# TC377TP_2.net
KiCad netlist of a schematic drawn in Altium Designer
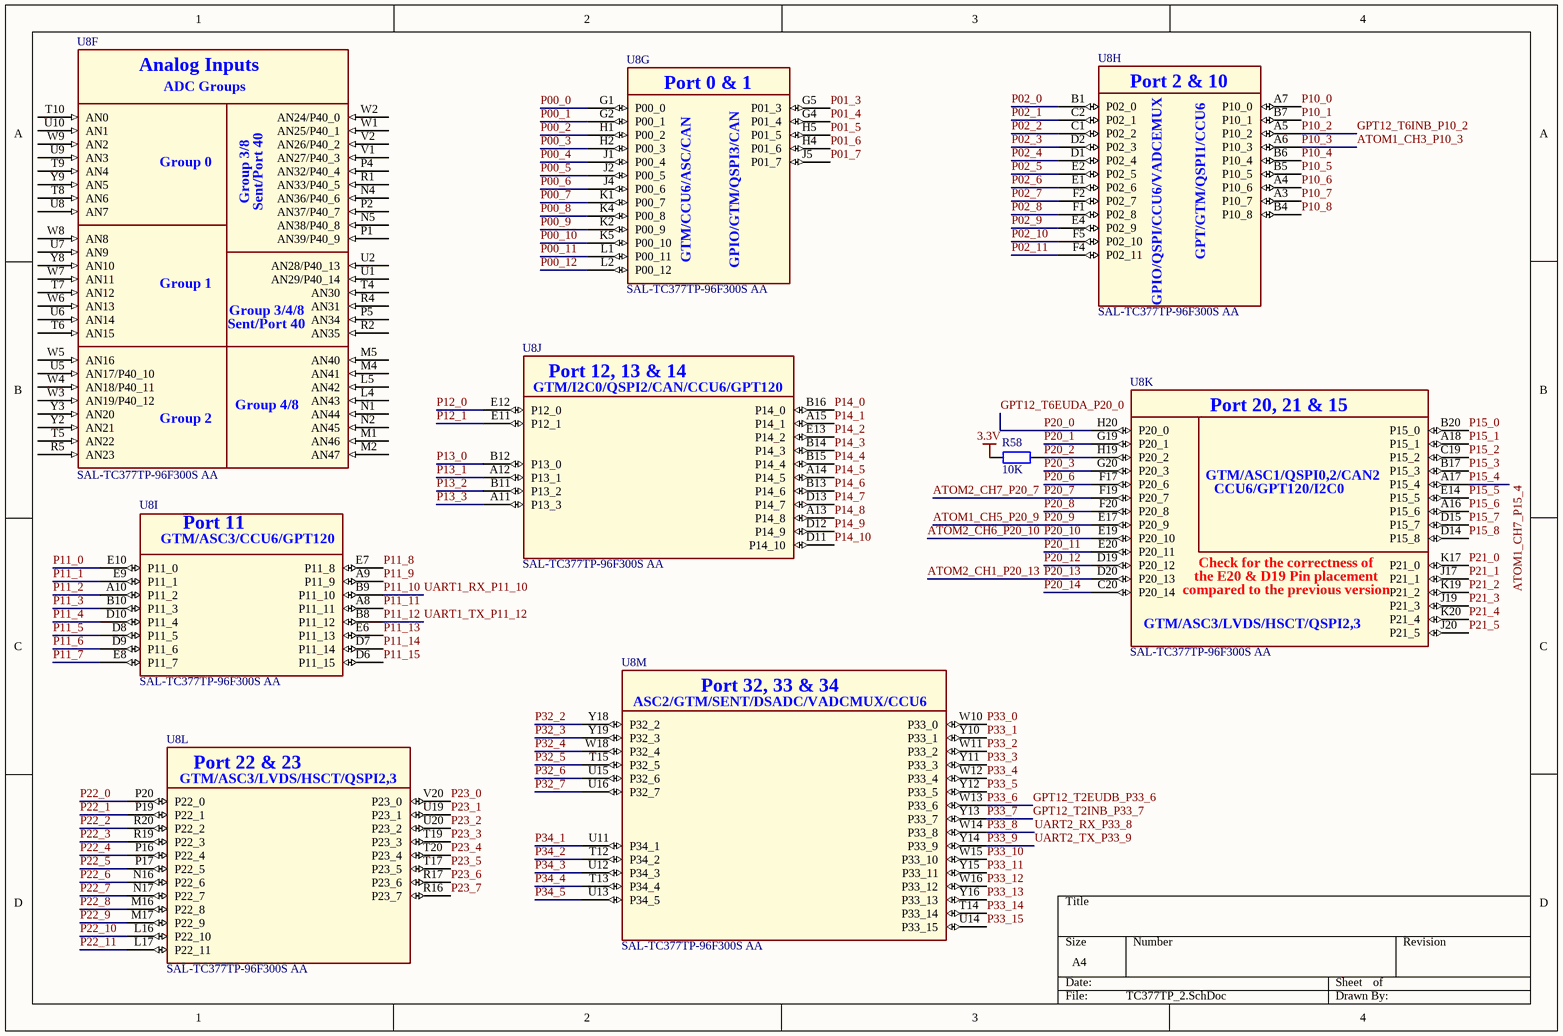
[diagram p0: TC377TP_2.SchDoc]

(export (version "E")
  (design (tool "Eeschema 10.0.6"))
  (components
    (comp (ref "R58")
      (value "10K")
      (footprint "R 0603_L")
      (description "贴片电阻")
      (fields (field (name "版权归属") "源创客"))
      (libsource (lib "3.1   - 电阻-电容-电感") (part "R"))
    )
    (comp (ref "U8")
      (value "SAL-TC377TP-96F300S AA")
      (footprint "BGA292C80P20X20")
      (description "32-Bit Single-Chip Microcontroller")
      (fields (field (name "MANUFACTURER") "Infineon Technologies"))
      (libsource (lib "SAL-TC377TP-96F300S AA") (part "SAL-TC377TP-96F300S AA"))
    )
  )
  (nets
    (net (code "1") (name "/ATOM1_CH3_P10_3") (class "Default")
      (node (ref "U8") (pin "A6") (pinfunction "P10_3_A6") (pintype "bidirectional"))
    )
    (net (code "2") (name "/ATOM1_CH5_P20_9") (class "Default")
      (node (ref "U8") (pin "E17") (pinfunction "P20_9_E17") (pintype "bidirectional"))
    )
    (net (code "3") (name "/ATOM1_CH7_P15_4") (class "Default")
      (node (ref "U8") (pin "A17") (pinfunction "P15_4_A17") (pintype "bidirectional"))
    )
    (net (code "4") (name "/ATOM2_CH1_P20_13") (class "Default")
      (node (ref "U8") (pin "D20") (pinfunction "P20_13_D20") (pintype "bidirectional"))
    )
    (net (code "5") (name "/ATOM2_CH6_P20_10") (class "Default")
      (node (ref "U8") (pin "E19") (pinfunction "P20_10_E19") (pintype "bidirectional"))
    )
    (net (code "6") (name "/ATOM2_CH7_P20_7") (class "Default")
      (node (ref "U8") (pin "F19") (pinfunction "P20_7_F19") (pintype "bidirectional"))
    )
    (net (code "7") (name "/GPT12_T2EUDB_P33_6") (class "Default")
      (node (ref "U8") (pin "W13") (pinfunction "P33_6_W13") (pintype "bidirectional"))
    )
    (net (code "8") (name "/GPT12_T2INB_P33_7") (class "Default")
      (node (ref "U8") (pin "Y13") (pinfunction "P33_7_Y13") (pintype "bidirectional"))
    )
    (net (code "9") (name "/GPT12_T6EUDA_P20_0") (class "Default")
      (node (ref "U8") (pin "H20") (pinfunction "P20_0_H20") (pintype "bidirectional"))
    )
    (net (code "10") (name "/GPT12_T6INB_P10_2") (class "Default")
      (node (ref "U8") (pin "A5") (pinfunction "P10_2_A5") (pintype "bidirectional"))
    )
    (net (code "11") (name "/P00_0") (class "Default")
      (node (ref "U8") (pin "G1") (pinfunction "P00_0_G1") (pintype "bidirectional"))
    )
    (net (code "12") (name "/P00_1") (class "Default")
      (node (ref "U8") (pin "G2") (pinfunction "P00_1_G2") (pintype "bidirectional"))
    )
    (net (code "13") (name "/P00_2") (class "Default")
      (node (ref "U8") (pin "H1") (pinfunction "P00_2_H1") (pintype "bidirectional"))
    )
    (net (code "14") (name "/P00_3") (class "Default")
      (node (ref "U8") (pin "H2") (pinfunction "P00_3_H2") (pintype "bidirectional"))
    )
    (net (code "15") (name "/P00_4") (class "Default")
      (node (ref "U8") (pin "J1") (pinfunction "P00_4_J1") (pintype "bidirectional"))
    )
    (net (code "16") (name "/P00_5") (class "Default")
      (node (ref "U8") (pin "J2") (pinfunction "P00_5_J2") (pintype "bidirectional"))
    )
    (net (code "17") (name "/P00_6") (class "Default")
      (node (ref "U8") (pin "J4") (pinfunction "P00_6_J4") (pintype "bidirectional"))
    )
    (net (code "18") (name "/P00_7") (class "Default")
      (node (ref "U8") (pin "K1") (pinfunction "P00_7_K1") (pintype "bidirectional"))
    )
    (net (code "19") (name "/P00_8") (class "Default")
      (node (ref "U8") (pin "K4") (pinfunction "P00_8_K4") (pintype "bidirectional"))
    )
    (net (code "20") (name "/P00_9") (class "Default")
      (node (ref "U8") (pin "K2") (pinfunction "P00_9_K2") (pintype "bidirectional"))
    )
    (net (code "21") (name "/P00_10") (class "Default")
      (node (ref "U8") (pin "K5") (pinfunction "P00_10_K5") (pintype "bidirectional"))
    )
    (net (code "22") (name "/P00_11") (class "Default")
      (node (ref "U8") (pin "L1") (pinfunction "P00_11_L1") (pintype "bidirectional"))
    )
    (net (code "23") (name "/P00_12") (class "Default")
      (node (ref "U8") (pin "L2") (pinfunction "P00_12_L2") (pintype "bidirectional"))
    )
    (net (code "24") (name "/P01_3") (class "Default")
      (node (ref "U8") (pin "G5") (pinfunction "P01_3_G5") (pintype "bidirectional"))
    )
    (net (code "25") (name "/P01_4") (class "Default")
      (node (ref "U8") (pin "G4") (pinfunction "P01_4_G4") (pintype "bidirectional"))
    )
    (net (code "26") (name "/P01_5") (class "Default")
      (node (ref "U8") (pin "H5") (pinfunction "P01_5_H5") (pintype "bidirectional"))
    )
    (net (code "27") (name "/P01_6") (class "Default")
      (node (ref "U8") (pin "H4") (pinfunction "P01_6_H4") (pintype "bidirectional"))
    )
    (net (code "28") (name "/P01_7") (class "Default")
      (node (ref "U8") (pin "J5") (pinfunction "P01_7_J5") (pintype "bidirectional"))
    )
    (net (code "29") (name "/P02_0") (class "Default")
      (node (ref "U8") (pin "B1") (pinfunction "P02_0_B1") (pintype "bidirectional"))
    )
    (net (code "30") (name "/P02_1") (class "Default")
      (node (ref "U8") (pin "C2") (pinfunction "P02_1_C2") (pintype "bidirectional"))
    )
    (net (code "31") (name "/P02_2") (class "Default")
      (node (ref "U8") (pin "C1") (pinfunction "P02_2_C1") (pintype "bidirectional"))
    )
    (net (code "32") (name "/P02_3") (class "Default")
      (node (ref "U8") (pin "D2") (pinfunction "P02_3_D2") (pintype "bidirectional"))
    )
    (net (code "33") (name "/P02_4") (class "Default")
      (node (ref "U8") (pin "D1") (pinfunction "P02_4_D1") (pintype "bidirectional"))
    )
    (net (code "34") (name "/P02_5") (class "Default")
      (node (ref "U8") (pin "E2") (pinfunction "P02_5_E2") (pintype "bidirectional"))
    )
    (net (code "35") (name "/P02_6") (class "Default")
      (node (ref "U8") (pin "E1") (pinfunction "P02_6_E1") (pintype "bidirectional"))
    )
    (net (code "36") (name "/P02_7") (class "Default")
      (node (ref "U8") (pin "F2") (pinfunction "P02_7_F2") (pintype "bidirectional"))
    )
    (net (code "37") (name "/P02_8") (class "Default")
      (node (ref "U8") (pin "F1") (pinfunction "P02_8_F1") (pintype "bidirectional"))
    )
    (net (code "38") (name "/P02_9") (class "Default")
      (node (ref "U8") (pin "E4") (pinfunction "P02_9_E4") (pintype "bidirectional"))
    )
    (net (code "39") (name "/P02_10") (class "Default")
      (node (ref "U8") (pin "F5") (pinfunction "P02_10_F5") (pintype "bidirectional"))
    )
    (net (code "40") (name "/P02_11") (class "Default")
      (node (ref "U8") (pin "F4") (pinfunction "P02_11_F4") (pintype "bidirectional"))
    )
    (net (code "41") (name "/P10_0") (class "Default")
      (node (ref "U8") (pin "A7") (pinfunction "P10_0_A7") (pintype "bidirectional"))
    )
    (net (code "42") (name "/P10_1") (class "Default")
      (node (ref "U8") (pin "B7") (pinfunction "P10_1_B7") (pintype "bidirectional"))
    )
    (net (code "43") (name "/P10_4") (class "Default")
      (node (ref "U8") (pin "B6") (pinfunction "P10_4_B6") (pintype "bidirectional"))
    )
    (net (code "44") (name "/P10_5") (class "Default")
      (node (ref "U8") (pin "B5") (pinfunction "P10_5_B5") (pintype "bidirectional"))
    )
    (net (code "45") (name "/P10_6") (class "Default")
      (node (ref "U8") (pin "A4") (pinfunction "P10_6_A4") (pintype "bidirectional"))
    )
    (net (code "46") (name "/P10_7") (class "Default")
      (node (ref "U8") (pin "A3") (pinfunction "P10_7_A3") (pintype "bidirectional"))
    )
    (net (code "47") (name "/P10_8") (class "Default")
      (node (ref "U8") (pin "B4") (pinfunction "P10_8_B4") (pintype "bidirectional"))
    )
    (net (code "48") (name "/P11_0") (class "Default")
      (node (ref "U8") (pin "E10") (pinfunction "P11_0_E10") (pintype "bidirectional"))
    )
    (net (code "49") (name "/P11_1") (class "Default")
      (node (ref "U8") (pin "E9") (pinfunction "P11_1_E9") (pintype "bidirectional"))
    )
    (net (code "50") (name "/P11_2") (class "Default")
      (node (ref "U8") (pin "A10") (pinfunction "P11_2_A10") (pintype "bidirectional"))
    )
    (net (code "51") (name "/P11_3") (class "Default")
      (node (ref "U8") (pin "B10") (pinfunction "P11_3_B10") (pintype "bidirectional"))
    )
    (net (code "52") (name "/P11_4") (class "Default")
      (node (ref "U8") (pin "D10") (pinfunction "P11_4_D10") (pintype "bidirectional"))
    )
    (net (code "53") (name "/P11_5") (class "Default")
      (node (ref "U8") (pin "D8") (pinfunction "P11_5_D8") (pintype "bidirectional"))
    )
    (net (code "54") (name "/P11_6") (class "Default")
      (node (ref "U8") (pin "D9") (pinfunction "P11_6_D9") (pintype "bidirectional"))
    )
    (net (code "55") (name "/P11_7") (class "Default")
      (node (ref "U8") (pin "E8") (pinfunction "P11_7_E8") (pintype "bidirectional"))
    )
    (net (code "56") (name "/P11_8") (class "Default")
      (node (ref "U8") (pin "E7") (pinfunction "P11_8_E7") (pintype "bidirectional"))
    )
    (net (code "57") (name "/P11_9") (class "Default")
      (node (ref "U8") (pin "A9") (pinfunction "P11_9_A9") (pintype "bidirectional"))
    )
    (net (code "58") (name "/P11_10") (class "Default")
      (node (ref "U8") (pin "B9") (pinfunction "P11_10_B9") (pintype "bidirectional"))
    )
    (net (code "59") (name "/P11_11") (class "Default")
      (node (ref "U8") (pin "A8") (pinfunction "P11_11_A8") (pintype "bidirectional"))
    )
    (net (code "60") (name "/P11_12") (class "Default")
      (node (ref "U8") (pin "B8") (pinfunction "P11_12_B8") (pintype "bidirectional"))
    )
    (net (code "61") (name "/P11_13") (class "Default")
      (node (ref "U8") (pin "E6") (pinfunction "P11_13_E6") (pintype "bidirectional"))
    )
    (net (code "62") (name "/P11_14") (class "Default")
      (node (ref "U8") (pin "D7") (pinfunction "P11_14_D7") (pintype "bidirectional"))
    )
    (net (code "63") (name "/P11_15") (class "Default")
      (node (ref "U8") (pin "D6") (pinfunction "P11_15_D6") (pintype "bidirectional"))
    )
    (net (code "64") (name "/P12_0") (class "Default")
      (node (ref "U8") (pin "E12") (pinfunction "P12_0_E12") (pintype "bidirectional"))
    )
    (net (code "65") (name "/P12_1") (class "Default")
      (node (ref "U8") (pin "E11") (pinfunction "P12_1_E11") (pintype "bidirectional"))
    )
    (net (code "66") (name "/P13_0") (class "Default")
      (node (ref "U8") (pin "B12") (pinfunction "P13_0_B12") (pintype "bidirectional"))
    )
    (net (code "67") (name "/P13_1") (class "Default")
      (node (ref "U8") (pin "A12") (pinfunction "P13_1_A12") (pintype "bidirectional"))
    )
    (net (code "68") (name "/P13_2") (class "Default")
      (node (ref "U8") (pin "B11") (pinfunction "P13_2_B11") (pintype "bidirectional"))
    )
    (net (code "69") (name "/P13_3") (class "Default")
      (node (ref "U8") (pin "A11") (pinfunction "P13_3_A11") (pintype "bidirectional"))
    )
    (net (code "70") (name "/P14_0") (class "Default")
      (node (ref "U8") (pin "B16") (pinfunction "P14_0_B16") (pintype "bidirectional"))
    )
    (net (code "71") (name "/P14_1") (class "Default")
      (node (ref "U8") (pin "A15") (pinfunction "P14_1_A15") (pintype "bidirectional"))
    )
    (net (code "72") (name "/P14_2") (class "Default")
      (node (ref "U8") (pin "E13") (pinfunction "P14_2_E13") (pintype "bidirectional"))
    )
    (net (code "73") (name "/P14_3") (class "Default")
      (node (ref "U8") (pin "B14") (pinfunction "P14_3_B14") (pintype "bidirectional"))
    )
    (net (code "74") (name "/P14_4") (class "Default")
      (node (ref "U8") (pin "B15") (pinfunction "P14_4_B15") (pintype "bidirectional"))
    )
    (net (code "75") (name "/P14_5") (class "Default")
      (node (ref "U8") (pin "A14") (pinfunction "P14_5_A14") (pintype "bidirectional"))
    )
    (net (code "76") (name "/P14_6") (class "Default")
      (node (ref "U8") (pin "B13") (pinfunction "P14_6_B13") (pintype "bidirectional"))
    )
    (net (code "77") (name "/P14_7") (class "Default")
      (node (ref "U8") (pin "D13") (pinfunction "P14_7_D13") (pintype "bidirectional"))
    )
    (net (code "78") (name "/P14_8") (class "Default")
      (node (ref "U8") (pin "A13") (pinfunction "P14_8_A13") (pintype "bidirectional"))
    )
    (net (code "79") (name "/P14_9") (class "Default")
      (node (ref "U8") (pin "D12") (pinfunction "P14_9_D12") (pintype "bidirectional"))
    )
    (net (code "80") (name "/P14_10") (class "Default")
      (node (ref "U8") (pin "D11") (pinfunction "P14_10_D11") (pintype "bidirectional"))
    )
    (net (code "81") (name "/P15_0") (class "Default")
      (node (ref "U8") (pin "B20") (pinfunction "P15_0_B20") (pintype "bidirectional"))
    )
    (net (code "82") (name "/P15_1") (class "Default")
      (node (ref "U8") (pin "A18") (pinfunction "P15_1_A18") (pintype "bidirectional"))
    )
    (net (code "83") (name "/P15_2") (class "Default")
      (node (ref "U8") (pin "C19") (pinfunction "P15_2_C19") (pintype "bidirectional"))
    )
    (net (code "84") (name "/P15_3") (class "Default")
      (node (ref "U8") (pin "B17") (pinfunction "P15_3_B17") (pintype "bidirectional"))
    )
    (net (code "85") (name "/P15_5") (class "Default")
      (node (ref "U8") (pin "E14") (pinfunction "P15_5_E14") (pintype "bidirectional"))
    )
    (net (code "86") (name "/P15_6") (class "Default")
      (node (ref "U8") (pin "A16") (pinfunction "P15_6_A16") (pintype "bidirectional"))
    )
    (net (code "87") (name "/P15_7") (class "Default")
      (node (ref "U8") (pin "D15") (pinfunction "P15_7_D15") (pintype "bidirectional"))
    )
    (net (code "88") (name "/P15_8") (class "Default")
      (node (ref "U8") (pin "D14") (pinfunction "P15_8_D14") (pintype "bidirectional"))
    )
    (net (code "89") (name "/P20_1") (class "Default")
      (node (ref "U8") (pin "G19") (pinfunction "P20_1_G19") (pintype "bidirectional"))
    )
    (net (code "90") (name "/P20_2") (class "Default")
      (node (ref "R58") (pin "1") (pinfunction "1_1") (pintype "passive"))
      (node (ref "U8") (pin "H19") (pinfunction "P20_2_H19") (pintype "bidirectional"))
    )
    (net (code "91") (name "/P20_3") (class "Default")
      (node (ref "U8") (pin "G20") (pinfunction "P20_3_G20") (pintype "bidirectional"))
    )
    (net (code "92") (name "/P20_6") (class "Default")
      (node (ref "U8") (pin "F17") (pinfunction "P20_6_F17") (pintype "bidirectional"))
    )
    (net (code "93") (name "/P20_8") (class "Default")
      (node (ref "U8") (pin "F20") (pinfunction "P20_8_F20") (pintype "bidirectional"))
    )
    (net (code "94") (name "/P20_11") (class "Default")
      (node (ref "U8") (pin "E20") (pinfunction "P20_11_E20") (pintype "bidirectional"))
    )
    (net (code "95") (name "/P20_12") (class "Default")
      (node (ref "U8") (pin "D19") (pinfunction "P20_12_D19") (pintype "bidirectional"))
    )
    (net (code "96") (name "/P20_14") (class "Default")
      (node (ref "U8") (pin "C20") (pinfunction "P20_14_C20") (pintype "bidirectional"))
    )
    (net (code "97") (name "/P21_0") (class "Default")
      (node (ref "U8") (pin "K17") (pinfunction "P21_0_K17") (pintype "bidirectional"))
    )
    (net (code "98") (name "/P21_1") (class "Default")
      (node (ref "U8") (pin "J17") (pinfunction "P21_1_J17") (pintype "bidirectional"))
    )
    (net (code "99") (name "/P21_2") (class "Default")
      (node (ref "U8") (pin "K19") (pinfunction "P21_2_K19") (pintype "bidirectional"))
    )
    (net (code "100") (name "/P21_3") (class "Default")
      (node (ref "U8") (pin "J19") (pinfunction "P21_3_J19") (pintype "bidirectional"))
    )
    (net (code "101") (name "/P21_4") (class "Default")
      (node (ref "U8") (pin "K20") (pinfunction "P21_4_K20") (pintype "bidirectional"))
    )
    (net (code "102") (name "/P21_5") (class "Default")
      (node (ref "U8") (pin "J20") (pinfunction "P21_5_J20") (pintype "bidirectional"))
    )
    (net (code "103") (name "/P22_0") (class "Default")
      (node (ref "U8") (pin "P20") (pinfunction "P22_0_P20") (pintype "bidirectional"))
    )
    (net (code "104") (name "/P22_1") (class "Default")
      (node (ref "U8") (pin "P19") (pinfunction "P22_1_P19") (pintype "bidirectional"))
    )
    (net (code "105") (name "/P22_2") (class "Default")
      (node (ref "U8") (pin "R20") (pinfunction "P22_2_R20") (pintype "bidirectional"))
    )
    (net (code "106") (name "/P22_3") (class "Default")
      (node (ref "U8") (pin "R19") (pinfunction "P22_3_R19") (pintype "bidirectional"))
    )
    (net (code "107") (name "/P22_4") (class "Default")
      (node (ref "U8") (pin "P16") (pinfunction "P22_4_P16") (pintype "bidirectional"))
    )
    (net (code "108") (name "/P22_5") (class "Default")
      (node (ref "U8") (pin "P17") (pinfunction "P22_5_P17") (pintype "bidirectional"))
    )
    (net (code "109") (name "/P22_6") (class "Default")
      (node (ref "U8") (pin "N16") (pinfunction "P22_6_N16") (pintype "bidirectional"))
    )
    (net (code "110") (name "/P22_7") (class "Default")
      (node (ref "U8") (pin "N17") (pinfunction "P22_7_N17") (pintype "bidirectional"))
    )
    (net (code "111") (name "/P22_8") (class "Default")
      (node (ref "U8") (pin "M16") (pinfunction "P22_8_M16") (pintype "bidirectional"))
    )
    (net (code "112") (name "/P22_9") (class "Default")
      (node (ref "U8") (pin "M17") (pinfunction "P22_9_M17") (pintype "bidirectional"))
    )
    (net (code "113") (name "/P22_10") (class "Default")
      (node (ref "U8") (pin "L16") (pinfunction "P22_10_L16") (pintype "bidirectional"))
    )
    (net (code "114") (name "/P22_11") (class "Default")
      (node (ref "U8") (pin "L17") (pinfunction "P22_11_L17") (pintype "bidirectional"))
    )
    (net (code "115") (name "/P23_0") (class "Default")
      (node (ref "U8") (pin "V20") (pinfunction "P23_0_V20") (pintype "bidirectional"))
    )
    (net (code "116") (name "/P23_1") (class "Default")
      (node (ref "U8") (pin "U19") (pinfunction "P23_1_U19") (pintype "bidirectional"))
    )
    (net (code "117") (name "/P23_2") (class "Default")
      (node (ref "U8") (pin "U20") (pinfunction "P23_2_U20") (pintype "bidirectional"))
    )
    (net (code "118") (name "/P23_3") (class "Default")
      (node (ref "U8") (pin "T19") (pinfunction "P23_3_T19") (pintype "bidirectional"))
    )
    (net (code "119") (name "/P23_4") (class "Default")
      (node (ref "U8") (pin "T20") (pinfunction "P23_4_T20") (pintype "bidirectional"))
    )
    (net (code "120") (name "/P23_5") (class "Default")
      (node (ref "U8") (pin "T17") (pinfunction "P23_5_T17") (pintype "bidirectional"))
    )
    (net (code "121") (name "/P23_6") (class "Default")
      (node (ref "U8") (pin "R17") (pinfunction "P23_6_R17") (pintype "bidirectional"))
    )
    (net (code "122") (name "/P23_7") (class "Default")
      (node (ref "U8") (pin "R16") (pinfunction "P23_7_R16") (pintype "bidirectional"))
    )
    (net (code "123") (name "/P32_2") (class "Default")
      (node (ref "U8") (pin "Y18") (pinfunction "P32_2_Y18") (pintype "bidirectional"))
    )
    (net (code "124") (name "/P32_3") (class "Default")
      (node (ref "U8") (pin "Y19") (pinfunction "P32_3_Y19") (pintype "bidirectional"))
    )
    (net (code "125") (name "/P32_4") (class "Default")
      (node (ref "U8") (pin "W18") (pinfunction "P32_4_W18") (pintype "bidirectional"))
    )
    (net (code "126") (name "/P32_5") (class "Default")
      (node (ref "U8") (pin "T15") (pinfunction "P32_5_T15") (pintype "bidirectional"))
    )
    (net (code "127") (name "/P32_6") (class "Default")
      (node (ref "U8") (pin "U15") (pinfunction "P32_6_U15") (pintype "bidirectional"))
    )
    (net (code "128") (name "/P32_7") (class "Default")
      (node (ref "U8") (pin "U16") (pinfunction "P32_7_U16") (pintype "bidirectional"))
    )
    (net (code "129") (name "/P33_0") (class "Default")
      (node (ref "U8") (pin "W10") (pinfunction "P33_0_W10") (pintype "bidirectional"))
    )
    (net (code "130") (name "/P33_1") (class "Default")
      (node (ref "U8") (pin "Y10") (pinfunction "P33_1_Y10") (pintype "bidirectional"))
    )
    (net (code "131") (name "/P33_2") (class "Default")
      (node (ref "U8") (pin "W11") (pinfunction "P33_2_W11") (pintype "bidirectional"))
    )
    (net (code "132") (name "/P33_3") (class "Default")
      (node (ref "U8") (pin "Y11") (pinfunction "P33_3_Y11") (pintype "bidirectional"))
    )
    (net (code "133") (name "/P33_4") (class "Default")
      (node (ref "U8") (pin "W12") (pinfunction "P33_4_W12") (pintype "bidirectional"))
    )
    (net (code "134") (name "/P33_5") (class "Default")
      (node (ref "U8") (pin "Y12") (pinfunction "P33_5_Y12") (pintype "bidirectional"))
    )
    (net (code "135") (name "/P33_8") (class "Default")
      (node (ref "U8") (pin "W14") (pinfunction "P33_8_W14") (pintype "bidirectional"))
    )
    (net (code "136") (name "/P33_9") (class "Default")
      (node (ref "U8") (pin "Y14") (pinfunction "P33_9_Y14") (pintype "bidirectional"))
    )
    (net (code "137") (name "/P33_10") (class "Default")
      (node (ref "U8") (pin "W15") (pinfunction "P33_10_W15") (pintype "bidirectional"))
    )
    (net (code "138") (name "/P33_11") (class "Default")
      (node (ref "U8") (pin "Y15") (pinfunction "P33_11_Y15") (pintype "bidirectional"))
    )
    (net (code "139") (name "/P33_12") (class "Default")
      (node (ref "U8") (pin "W16") (pinfunction "P33_12_W16") (pintype "bidirectional"))
    )
    (net (code "140") (name "/P33_13") (class "Default")
      (node (ref "U8") (pin "Y16") (pinfunction "P33_13_Y16") (pintype "bidirectional"))
    )
    (net (code "141") (name "/P33_14") (class "Default")
      (node (ref "U8") (pin "T14") (pinfunction "P33_14_T14") (pintype "bidirectional"))
    )
    (net (code "142") (name "/P33_15") (class "Default")
      (node (ref "U8") (pin "U14") (pinfunction "P33_15_U14") (pintype "bidirectional"))
    )
    (net (code "143") (name "/P34_1") (class "Default")
      (node (ref "U8") (pin "U11") (pinfunction "P34_1_U11") (pintype "bidirectional"))
    )
    (net (code "144") (name "/P34_2") (class "Default")
      (node (ref "U8") (pin "T12") (pinfunction "P34_2_T12") (pintype "bidirectional"))
    )
    (net (code "145") (name "/P34_3") (class "Default")
      (node (ref "U8") (pin "U12") (pinfunction "P34_3_U12") (pintype "bidirectional"))
    )
    (net (code "146") (name "/P34_4") (class "Default")
      (node (ref "U8") (pin "T13") (pinfunction "P34_4_T13") (pintype "bidirectional"))
    )
    (net (code "147") (name "/P34_5") (class "Default")
      (node (ref "U8") (pin "U13") (pinfunction "P34_5_U13") (pintype "bidirectional"))
    )
    (net (code "148") (name "3.3V") (class "Default")
      (node (ref "R58") (pin "2") (pinfunction "2_2") (pintype "passive"))
    )
    (net (code "149") (name "unconnected-(U8F-AN0-PadT10)") (class "Default")
      (node (ref "U8") (pin "T10") (pinfunction "AN0_T10") (pintype "input"))
    )
    (net (code "150") (name "unconnected-(U8F-AN1-PadU10)") (class "Default")
      (node (ref "U8") (pin "U10") (pinfunction "AN1_U10") (pintype "input"))
    )
    (net (code "151") (name "unconnected-(U8F-AN2-PadW9)") (class "Default")
      (node (ref "U8") (pin "W9") (pinfunction "AN2_W9") (pintype "input"))
    )
    (net (code "152") (name "unconnected-(U8F-AN3-PadU9)") (class "Default")
      (node (ref "U8") (pin "U9") (pinfunction "AN3_U9") (pintype "input"))
    )
    (net (code "153") (name "unconnected-(U8F-AN4-PadT9)") (class "Default")
      (node (ref "U8") (pin "T9") (pinfunction "AN4_T9") (pintype "input"))
    )
    (net (code "154") (name "unconnected-(U8F-AN5-PadY9)") (class "Default")
      (node (ref "U8") (pin "Y9") (pinfunction "AN5_Y9") (pintype "input"))
    )
    (net (code "155") (name "unconnected-(U8F-AN6-PadT8)") (class "Default")
      (node (ref "U8") (pin "T8") (pinfunction "AN6_T8") (pintype "input"))
    )
    (net (code "156") (name "unconnected-(U8F-AN7-PadU8)") (class "Default")
      (node (ref "U8") (pin "U8") (pinfunction "AN7_U8") (pintype "input"))
    )
    (net (code "157") (name "unconnected-(U8F-AN8-PadW8)") (class "Default")
      (node (ref "U8") (pin "W8") (pinfunction "AN8_W8") (pintype "input"))
    )
    (net (code "158") (name "unconnected-(U8F-AN9-PadU7)") (class "Default")
      (node (ref "U8") (pin "U7") (pinfunction "AN9_U7") (pintype "input"))
    )
    (net (code "159") (name "unconnected-(U8F-AN10-PadY8)") (class "Default")
      (node (ref "U8") (pin "Y8") (pinfunction "AN10_Y8") (pintype "input"))
    )
    (net (code "160") (name "unconnected-(U8F-AN11-PadW7)") (class "Default")
      (node (ref "U8") (pin "W7") (pinfunction "AN11_W7") (pintype "input"))
    )
    (net (code "161") (name "unconnected-(U8F-AN12-PadT7)") (class "Default")
      (node (ref "U8") (pin "T7") (pinfunction "AN12_T7") (pintype "input"))
    )
    (net (code "162") (name "unconnected-(U8F-AN13-PadW6)") (class "Default")
      (node (ref "U8") (pin "W6") (pinfunction "AN13_W6") (pintype "input"))
    )
    (net (code "163") (name "unconnected-(U8F-AN14-PadU6)") (class "Default")
      (node (ref "U8") (pin "U6") (pinfunction "AN14_U6") (pintype "input"))
    )
    (net (code "164") (name "unconnected-(U8F-AN15-PadT6)") (class "Default")
      (node (ref "U8") (pin "T6") (pinfunction "AN15_T6") (pintype "input"))
    )
    (net (code "165") (name "unconnected-(U8F-AN16-PadW5)") (class "Default")
      (node (ref "U8") (pin "W5") (pinfunction "AN16_W5") (pintype "input"))
    )
    (net (code "166") (name "unconnected-(U8F-AN17{slash}P40_10-PadU5)") (class "Default")
      (node (ref "U8") (pin "U5") (pinfunction "AN17/P40_10_U5") (pintype "input"))
    )
    (net (code "167") (name "unconnected-(U8F-AN18{slash}P40_11-PadW4)") (class "Default")
      (node (ref "U8") (pin "W4") (pinfunction "AN18/P40_11_W4") (pintype "input"))
    )
    (net (code "168") (name "unconnected-(U8F-AN19{slash}P40_12-PadW3)") (class "Default")
      (node (ref "U8") (pin "W3") (pinfunction "AN19/P40_12_W3") (pintype "input"))
    )
    (net (code "169") (name "unconnected-(U8F-AN20-PadY3)") (class "Default")
      (node (ref "U8") (pin "Y3") (pinfunction "AN20_Y3") (pintype "input"))
    )
    (net (code "170") (name "unconnected-(U8F-AN21-PadY2)") (class "Default")
      (node (ref "U8") (pin "Y2") (pinfunction "AN21_Y2") (pintype "input"))
    )
    (net (code "171") (name "unconnected-(U8F-AN22-PadT5)") (class "Default")
      (node (ref "U8") (pin "T5") (pinfunction "AN22_T5") (pintype "input"))
    )
    (net (code "172") (name "unconnected-(U8F-AN23-PadR5)") (class "Default")
      (node (ref "U8") (pin "R5") (pinfunction "AN23_R5") (pintype "input"))
    )
    (net (code "173") (name "unconnected-(U8F-AN24{slash}P40_0-PadW2)") (class "Default")
      (node (ref "U8") (pin "W2") (pinfunction "AN24/P40_0_W2") (pintype "input"))
    )
    (net (code "174") (name "unconnected-(U8F-AN25{slash}P40_1-PadW1)") (class "Default")
      (node (ref "U8") (pin "W1") (pinfunction "AN25/P40_1_W1") (pintype "input"))
    )
    (net (code "175") (name "unconnected-(U8F-AN26{slash}P40_2-PadV2)") (class "Default")
      (node (ref "U8") (pin "V2") (pinfunction "AN26/P40_2_V2") (pintype "input"))
    )
    (net (code "176") (name "unconnected-(U8F-AN27{slash}P40_3-PadV1)") (class "Default")
      (node (ref "U8") (pin "V1") (pinfunction "AN27/P40_3_V1") (pintype "input"))
    )
    (net (code "177") (name "unconnected-(U8F-AN28{slash}P40_13-PadU2)") (class "Default")
      (node (ref "U8") (pin "U2") (pinfunction "AN28/P40_13_U2") (pintype "input"))
    )
    (net (code "178") (name "unconnected-(U8F-AN29{slash}P40_14-PadU1)") (class "Default")
      (node (ref "U8") (pin "U1") (pinfunction "AN29/P40_14_U1") (pintype "input"))
    )
    (net (code "179") (name "unconnected-(U8F-AN30-PadT4)") (class "Default")
      (node (ref "U8") (pin "T4") (pinfunction "AN30_T4") (pintype "input"))
    )
    (net (code "180") (name "unconnected-(U8F-AN31-PadR4)") (class "Default")
      (node (ref "U8") (pin "R4") (pinfunction "AN31_R4") (pintype "input"))
    )
    (net (code "181") (name "unconnected-(U8F-AN32{slash}P40_4-PadP4)") (class "Default")
      (node (ref "U8") (pin "P4") (pinfunction "AN32/P40_4_P4") (pintype "input"))
    )
    (net (code "182") (name "unconnected-(U8F-AN33{slash}P40_5-PadR1)") (class "Default")
      (node (ref "U8") (pin "R1") (pinfunction "AN33/P40_5_R1") (pintype "input"))
    )
    (net (code "183") (name "unconnected-(U8F-AN34-PadP5)") (class "Default")
      (node (ref "U8") (pin "P5") (pinfunction "AN34_P5") (pintype "input"))
    )
    (net (code "184") (name "unconnected-(U8F-AN35-PadR2)") (class "Default")
      (node (ref "U8") (pin "R2") (pinfunction "AN35_R2") (pintype "input"))
    )
    (net (code "185") (name "unconnected-(U8F-AN36{slash}P40_6-PadN4)") (class "Default")
      (node (ref "U8") (pin "N4") (pinfunction "AN36/P40_6_N4") (pintype "input"))
    )
    (net (code "186") (name "unconnected-(U8F-AN37{slash}P40_7-PadP2)") (class "Default")
      (node (ref "U8") (pin "P2") (pinfunction "AN37/P40_7_P2") (pintype "input"))
    )
    (net (code "187") (name "unconnected-(U8F-AN38{slash}P40_8-PadN5)") (class "Default")
      (node (ref "U8") (pin "N5") (pinfunction "AN38/P40_8_N5") (pintype "input"))
    )
    (net (code "188") (name "unconnected-(U8F-AN39{slash}P40_9-PadP1)") (class "Default")
      (node (ref "U8") (pin "P1") (pinfunction "AN39/P40_9_P1") (pintype "input"))
    )
    (net (code "189") (name "unconnected-(U8F-AN40-PadM5)") (class "Default")
      (node (ref "U8") (pin "M5") (pinfunction "AN40_M5") (pintype "input"))
    )
    (net (code "190") (name "unconnected-(U8F-AN41-PadM4)") (class "Default")
      (node (ref "U8") (pin "M4") (pinfunction "AN41_M4") (pintype "input"))
    )
    (net (code "191") (name "unconnected-(U8F-AN42-PadL5)") (class "Default")
      (node (ref "U8") (pin "L5") (pinfunction "AN42_L5") (pintype "input"))
    )
    (net (code "192") (name "unconnected-(U8F-AN43-PadL4)") (class "Default")
      (node (ref "U8") (pin "L4") (pinfunction "AN43_L4") (pintype "input"))
    )
    (net (code "193") (name "unconnected-(U8F-AN44-PadN1)") (class "Default")
      (node (ref "U8") (pin "N1") (pinfunction "AN44_N1") (pintype "input"))
    )
    (net (code "194") (name "unconnected-(U8F-AN45-PadN2)") (class "Default")
      (node (ref "U8") (pin "N2") (pinfunction "AN45_N2") (pintype "input"))
    )
    (net (code "195") (name "unconnected-(U8F-AN46-PadM1)") (class "Default")
      (node (ref "U8") (pin "M1") (pinfunction "AN46_M1") (pintype "input"))
    )
    (net (code "196") (name "unconnected-(U8F-AN47-PadM2)") (class "Default")
      (node (ref "U8") (pin "M2") (pinfunction "AN47_M2") (pintype "input"))
    )
  )
)
